# Righ_CH.net
KiCad netlist of a schematic drawn in Altium Designer
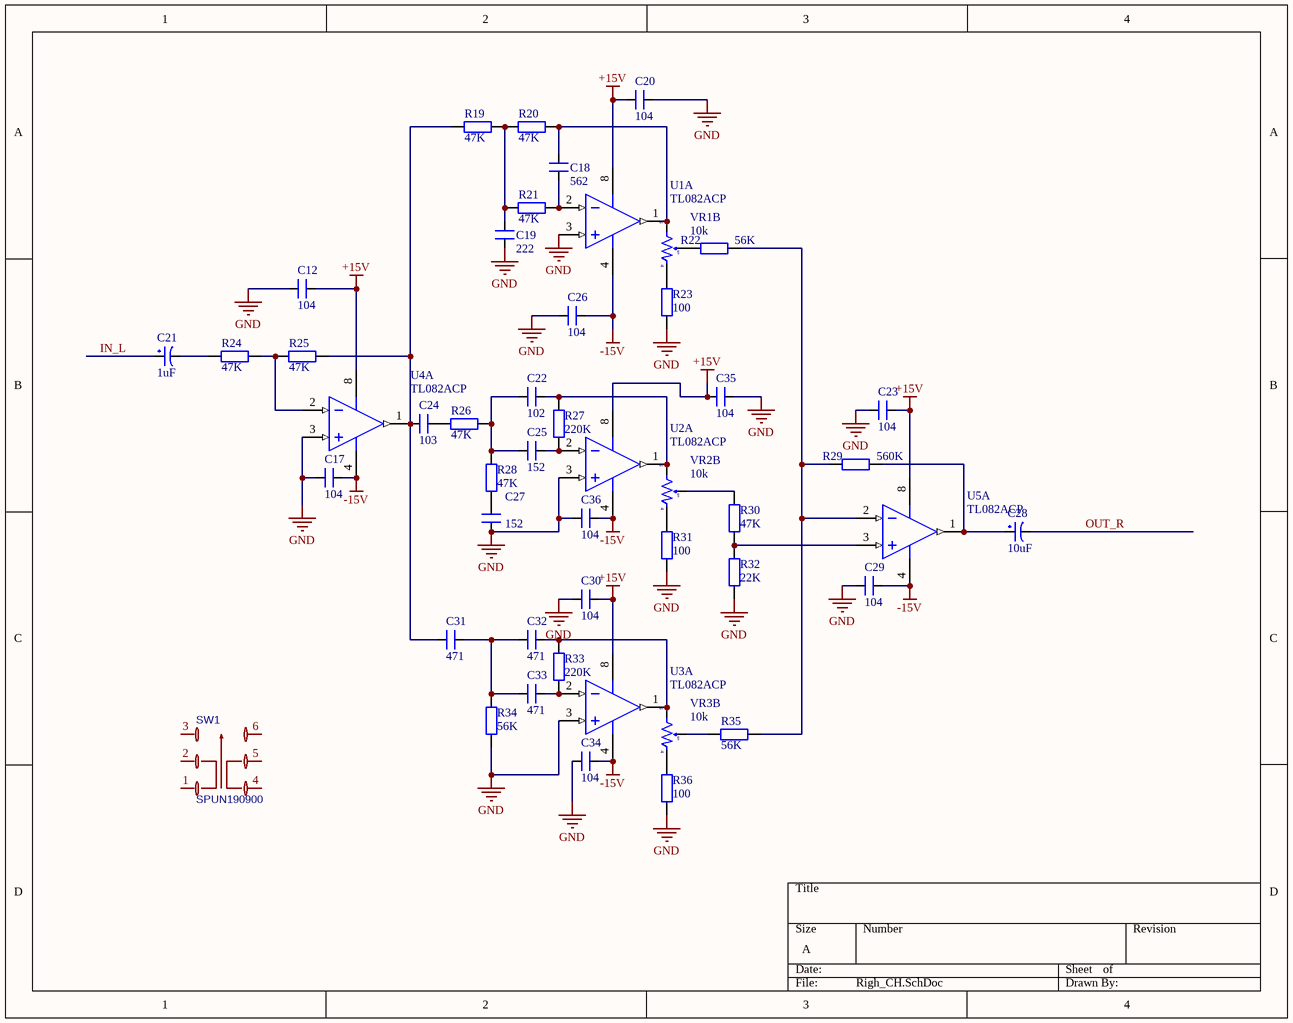
[diagram p0: Righ_CH.SchDoc]

(export (version "E")
  (design (tool "Eeschema 10.0.6"))
  (components
    (comp (ref "C12")
      (value "104")
      (footprint "TU_GOM(104-->105pF)")
      (libsource (lib "MH_DA_THU_VIEN_16122016") (part "TU_MICA_ 104 100V(2A104J)_MH"))
    )
    (comp (ref "C17")
      (value "104")
      (footprint "TU_GOM(104-->105pF)")
      (libsource (lib "MH_DA_THU_VIEN_16122016") (part "TU_MICA_ 104 100V(2A104J)_MH"))
    )
    (comp (ref "C18")
      (value "562")
      (footprint "WIMA-FKP-2-1nF")
      (libsource (lib "MH_DA_THU_VIEN_16122016") (part "TU_MICA_ 104 100V(2A104J)_MH"))
    )
    (comp (ref "C19")
      (value "222")
      (footprint "WIMA-FKP-2-1nF")
      (libsource (lib "MH_DA_THU_VIEN_16122016") (part "TU_MICA_ 104 100V(2A104J)_MH"))
    )
    (comp (ref "C20")
      (value "104")
      (footprint "TU_GOM(104-->105pF)")
      (libsource (lib "MH_DA_THU_VIEN_16122016") (part "TU_MICA_ 104 100V(2A104J)_MH"))
    )
    (comp (ref "C21")
      (value "1uF")
      (footprint "CP1/3.0")
      (description "TU_HOA_4.7uF_100V_MH")
      (libsource (lib "MH_DA_THU_VIEN_16122016") (part "TU_HOA_4.7uF_100V_MH"))
    )
    (comp (ref "C22")
      (value "102")
      (footprint "WIMA-FKP-2-1nF")
      (libsource (lib "MH_DA_THU_VIEN_16122016") (part "TU_MICA_ 104 100V(2A104J)_MH"))
    )
    (comp (ref "C23")
      (value "104")
      (footprint "TU_GOM(104-->105pF)")
      (libsource (lib "MH_DA_THU_VIEN_16122016") (part "TU_MICA_ 104 100V(2A104J)_MH"))
    )
    (comp (ref "C24")
      (value "103")
      (footprint "WIMA-FKP-2-1nF")
      (libsource (lib "MH_DA_THU_VIEN_16122016") (part "TU_MICA_ 104 100V(2A104J)_MH"))
    )
    (comp (ref "C25")
      (value "152")
      (footprint "WIMA-FKP-2-1nF")
      (libsource (lib "MH_DA_THU_VIEN_16122016") (part "TU_MICA_ 104 100V(2A104J)_MH"))
    )
    (comp (ref "C26")
      (value "104")
      (footprint "TU_GOM(104-->105pF)")
      (libsource (lib "MH_DA_THU_VIEN_16122016") (part "TU_MICA_ 104 100V(2A104J)_MH"))
    )
    (comp (ref "C27")
      (value "152")
      (footprint "WIMA-FKP-2-1nF")
      (libsource (lib "MH_DA_THU_VIEN_16122016") (part "TU_MICA_ 104 100V(2A104J)_MH"))
    )
    (comp (ref "C28")
      (value "10uF")
      (footprint "CP1/3.0")
      (description "TU_HOA_4.7uF_100V_MH")
      (libsource (lib "MH_DA_THU_VIEN_16122016") (part "TU_HOA_4.7uF_100V_MH"))
    )
    (comp (ref "C29")
      (value "104")
      (footprint "TU_GOM(104-->105pF)")
      (libsource (lib "MH_DA_THU_VIEN_16122016") (part "TU_MICA_ 104 100V(2A104J)_MH"))
    )
    (comp (ref "C30")
      (value "104")
      (footprint "TU_GOM(104-->105pF)")
      (libsource (lib "MH_DA_THU_VIEN_16122016") (part "TU_MICA_ 104 100V(2A104J)_MH"))
    )
    (comp (ref "C31")
      (value "471")
      (footprint "WIMA-FKP-2-1nF")
      (libsource (lib "MH_DA_THU_VIEN_16122016") (part "TU_MICA_ 104 100V(2A104J)_MH"))
    )
    (comp (ref "C32")
      (value "471")
      (footprint "WIMA-FKP-2-1nF")
      (libsource (lib "MH_DA_THU_VIEN_16122016") (part "TU_MICA_ 104 100V(2A104J)_MH"))
    )
    (comp (ref "C33")
      (value "471")
      (footprint "WIMA-FKP-2-1nF")
      (libsource (lib "MH_DA_THU_VIEN_16122016") (part "TU_MICA_ 104 100V(2A104J)_MH"))
    )
    (comp (ref "C34")
      (value "104")
      (footprint "TU_GOM(104-->105pF)")
      (libsource (lib "MH_DA_THU_VIEN_16122016") (part "TU_MICA_ 104 100V(2A104J)_MH"))
    )
    (comp (ref "C35")
      (value "104")
      (footprint "TU_GOM(104-->105pF)")
      (libsource (lib "MH_DA_THU_VIEN_16122016") (part "TU_MICA_ 104 100V(2A104J)_MH"))
    )
    (comp (ref "C36")
      (value "104")
      (footprint "TU_GOM(104-->105pF)")
      (libsource (lib "MH_DA_THU_VIEN_16122016") (part "TU_MICA_ 104 100V(2A104J)_MH"))
    )
    (comp (ref "R19")
      (value "47K")
      (footprint "TRO_VACH_ 1/4W")
      (description "Resistor")
      (fields (field (name "PUBLISHER") "Altium Limited"))
      (libsource (lib "") (part "TRO_VACH_1/2W_MH_2"))
    )
    (comp (ref "R20")
      (value "47K")
      (footprint "TRO_VACH_ 1/4W")
      (description "Resistor")
      (fields (field (name "PUBLISHER") "Altium Limited"))
      (libsource (lib "") (part "TRO_VACH_1/2W_MH_2"))
    )
    (comp (ref "R21")
      (value "47K")
      (footprint "TRO_VACH_ 1/4W")
      (description "Resistor")
      (fields (field (name "PUBLISHER") "Altium Limited"))
      (libsource (lib "") (part "TRO_VACH_1/2W_MH_2"))
    )
    (comp (ref "R22")
      (value "56K")
      (footprint "TRO_VACH_ 1/4W")
      (description "Resistor")
      (fields (field (name "PUBLISHER") "Altium Limited"))
      (libsource (lib "") (part "TRO_VACH_1/2W_MH_1"))
    )
    (comp (ref "R23")
      (value "100")
      (footprint "TRO_VACH_ 1/4W")
      (description "Resistor")
      (fields (field (name "PUBLISHER") "Altium Limited"))
      (libsource (lib "MH_DA_THU_VIEN_16122016") (part "TRO_VACH_1/2W_MH"))
    )
    (comp (ref "R24")
      (value "47K")
      (footprint "TRO_VACH_ 1/4W")
      (description "Resistor")
      (fields (field (name "PUBLISHER") "Altium Limited"))
      (libsource (lib "") (part "TRO_VACH_1/2W_MH_2"))
    )
    (comp (ref "R25")
      (value "47K")
      (footprint "TRO_VACH_ 1/4W")
      (description "Resistor")
      (fields (field (name "PUBLISHER") "Altium Limited"))
      (libsource (lib "") (part "TRO_VACH_1/2W_MH_2"))
    )
    (comp (ref "R26")
      (value "47K")
      (footprint "TRO_VACH_ 1/4W")
      (description "Resistor")
      (fields (field (name "PUBLISHER") "Altium Limited"))
      (libsource (lib "") (part "TRO_VACH_1/2W_MH_1"))
    )
    (comp (ref "R27")
      (value "220K")
      (footprint "TRO_VACH_ 1/4W")
      (description "Resistor")
      (fields (field (name "PUBLISHER") "Altium Limited"))
      (libsource (lib "MH_DA_THU_VIEN_16122016") (part "TRO_VACH_1/2W_MH"))
    )
    (comp (ref "R28")
      (value "47K")
      (footprint "TRO_VACH_ 1/4W")
      (description "Resistor")
      (fields (field (name "PUBLISHER") "Altium Limited"))
      (libsource (lib "MH_DA_THU_VIEN_16122016") (part "TRO_VACH_1/2W_MH"))
    )
    (comp (ref "R29")
      (value "560K")
      (footprint "TRO_VACH_ 1/4W")
      (description "Resistor")
      (fields (field (name "PUBLISHER") "Altium Limited"))
      (libsource (lib "") (part "TRO_VACH_1/2W_MH_1"))
    )
    (comp (ref "R30")
      (value "47K")
      (footprint "TRO_VACH_ 1/4W")
      (description "Resistor")
      (fields (field (name "PUBLISHER") "Altium Limited"))
      (libsource (lib "MH_DA_THU_VIEN_16122016") (part "TRO_VACH_1/2W_MH"))
    )
    (comp (ref "R31")
      (value "100")
      (footprint "TRO_VACH_ 1/4W")
      (description "Resistor")
      (fields (field (name "PUBLISHER") "Altium Limited"))
      (libsource (lib "MH_DA_THU_VIEN_16122016") (part "TRO_VACH_1/2W_MH"))
    )
    (comp (ref "R32")
      (value "22K")
      (footprint "TRO_VACH_ 1/4W")
      (description "Resistor")
      (fields (field (name "PUBLISHER") "Altium Limited"))
      (libsource (lib "MH_DA_THU_VIEN_16122016") (part "TRO_VACH_1/2W_MH"))
    )
    (comp (ref "R33")
      (value "220K")
      (footprint "TRO_VACH_ 1/4W")
      (description "Resistor")
      (fields (field (name "PUBLISHER") "Altium Limited"))
      (libsource (lib "MH_DA_THU_VIEN_16122016") (part "TRO_VACH_1/2W_MH"))
    )
    (comp (ref "R34")
      (value "56K")
      (footprint "TRO_VACH_ 1/4W")
      (description "Resistor")
      (fields (field (name "PUBLISHER") "Altium Limited"))
      (libsource (lib "MH_DA_THU_VIEN_16122016") (part "TRO_VACH_1/2W_MH"))
    )
    (comp (ref "R35")
      (value "56K")
      (footprint "TRO_VACH_ 1/4W")
      (description "Resistor")
      (fields (field (name "PUBLISHER") "Altium Limited"))
      (libsource (lib "") (part "TRO_VACH_1/2W_MH_1"))
    )
    (comp (ref "R36")
      (value "100")
      (footprint "TRO_VACH_ 1/4W")
      (description "Resistor")
      (fields (field (name "PUBLISHER") "Altium Limited"))
      (libsource (lib "MH_DA_THU_VIEN_16122016") (part "TRO_VACH_1/2W_MH"))
    )
    (comp (ref "SW1")
      (value "SPUN190900")
      (footprint "SW-DIP-P42X10")
      (fields (field (name "BOM_SUPPLIER PART") "C278339") (field (name "CONTRIBUTOR") "LCSC"))
      (libsource (lib "Schlib1") (part "SPUN190900"))
    )
    (comp (ref "U1")
      (value "TL082ACP")
      (footprint "DIP8")
      (description "JFET-Input Operational Amplifier")
      (fields (field (name "PUBLISHER") "Altium Limited"))
      (libsource (lib "Schlib1") (part "TL082ACP"))
    )
    (comp (ref "U2")
      (value "TL082ACP")
      (footprint "DIP8")
      (description "JFET-Input Operational Amplifier")
      (fields (field (name "PUBLISHER") "Altium Limited"))
      (libsource (lib "Schlib1") (part "TL082ACP"))
    )
    (comp (ref "U3")
      (value "TL082ACP")
      (footprint "DIP8")
      (description "JFET-Input Operational Amplifier")
      (fields (field (name "PUBLISHER") "Altium Limited"))
      (libsource (lib "Schlib1") (part "TL082ACP"))
    )
    (comp (ref "U4")
      (value "TL082ACP")
      (footprint "DIP8")
      (description "JFET-Input Operational Amplifier")
      (fields (field (name "PUBLISHER") "Altium Limited"))
      (libsource (lib "Schlib1") (part "TL082ACP"))
    )
    (comp (ref "U5")
      (value "TL082ACP")
      (footprint "DIP8")
      (description "JFET-Input Operational Amplifier")
      (fields (field (name "PUBLISHER") "Altium Limited"))
      (libsource (lib "Schlib1") (part "TL082ACP"))
    )
    (comp (ref "VR1")
      (value "10k")
      (footprint "9011")
      (description "Triet Ap Doi 10k")
      (libsource (lib "Schlib1") (part "Triet Ap Doi 10k_MH"))
    )
    (comp (ref "VR2")
      (value "10k")
      (footprint "9011")
      (description "Triet Ap Doi 10k")
      (libsource (lib "Schlib1") (part "Triet Ap Doi 10k_MH"))
    )
    (comp (ref "VR3")
      (value "10k")
      (footprint "9011")
      (description "Triet Ap Doi 10k")
      (libsource (lib "Schlib1") (part "Triet Ap Doi 10k_MH"))
    )
  )
  (nets
    (net (code "1") (name "+15V") (class "Default")
      (node (ref "C12") (pin "2") (pinfunction "2_2") (pintype "passive"))
      (node (ref "C20") (pin "1") (pinfunction "1_1") (pintype "passive"))
      (node (ref "C23") (pin "2") (pinfunction "2_2") (pintype "passive"))
      (node (ref "C30") (pin "2") (pinfunction "2_2") (pintype "passive"))
      (node (ref "C35") (pin "2") (pinfunction "2_2") (pintype "passive"))
      (node (ref "U1") (pin "8") (pinfunction "V+_8") (pintype "power_in"))
      (node (ref "U2") (pin "8") (pinfunction "V+_8") (pintype "power_in"))
      (node (ref "U3") (pin "8") (pinfunction "V+_8") (pintype "power_in"))
      (node (ref "U4") (pin "8") (pinfunction "V+_8") (pintype "power_in"))
      (node (ref "U5") (pin "8") (pinfunction "V+_8") (pintype "power_in"))
    )
    (net (code "2") (name "-15V") (class "Default")
      (node (ref "C17") (pin "2") (pinfunction "2_2") (pintype "passive"))
      (node (ref "C26") (pin "2") (pinfunction "2_2") (pintype "passive"))
      (node (ref "C29") (pin "2") (pinfunction "2_2") (pintype "passive"))
      (node (ref "C34") (pin "2") (pinfunction "2_2") (pintype "passive"))
      (node (ref "C36") (pin "1") (pinfunction "1_1") (pintype "passive"))
      (node (ref "U1") (pin "4") (pinfunction "V-_4") (pintype "power_in"))
      (node (ref "U2") (pin "4") (pinfunction "V-_4") (pintype "power_in"))
      (node (ref "U3") (pin "4") (pinfunction "V-_4") (pintype "power_in"))
      (node (ref "U4") (pin "4") (pinfunction "V-_4") (pintype "power_in"))
      (node (ref "U5") (pin "4") (pinfunction "V-_4") (pintype "power_in"))
    )
    (net (code "3") (name "/IN_L") (class "Default")
      (node (ref "C21") (pin "1") (pinfunction "1_1") (pintype "passive"))
    )
    (net (code "4") (name "/OUT_R") (class "Default")
      (node (ref "C28") (pin "2") (pinfunction "2_2") (pintype "passive"))
    )
    (net (code "5") (name "GND") (class "Default")
      (node (ref "C12") (pin "1") (pinfunction "1_1") (pintype "passive"))
      (node (ref "C17") (pin "1") (pinfunction "1_1") (pintype "passive"))
      (node (ref "C19") (pin "1") (pinfunction "1_1") (pintype "passive"))
      (node (ref "C20") (pin "2") (pinfunction "2_2") (pintype "passive"))
      (node (ref "C23") (pin "1") (pinfunction "1_1") (pintype "passive"))
      (node (ref "C26") (pin "1") (pinfunction "1_1") (pintype "passive"))
      (node (ref "C27") (pin "2") (pinfunction "2_2") (pintype "passive"))
      (node (ref "C29") (pin "1") (pinfunction "1_1") (pintype "passive"))
      (node (ref "C30") (pin "1") (pinfunction "1_1") (pintype "passive"))
      (node (ref "C34") (pin "1") (pinfunction "1_1") (pintype "passive"))
      (node (ref "C35") (pin "1") (pinfunction "1_1") (pintype "passive"))
      (node (ref "C36") (pin "2") (pinfunction "2_2") (pintype "passive"))
      (node (ref "R23") (pin "1") (pinfunction "1_1") (pintype "passive"))
      (node (ref "R31") (pin "1") (pinfunction "1_1") (pintype "passive"))
      (node (ref "R32") (pin "1") (pinfunction "1_1") (pintype "passive"))
      (node (ref "R34") (pin "1") (pinfunction "1_1") (pintype "passive"))
      (node (ref "R36") (pin "1") (pinfunction "1_1") (pintype "passive"))
      (node (ref "U1") (pin "3") (pinfunction "IN+_3") (pintype "input"))
      (node (ref "U2") (pin "3") (pinfunction "IN+_3") (pintype "input"))
      (node (ref "U3") (pin "3") (pinfunction "IN+_3") (pintype "input"))
      (node (ref "U4") (pin "3") (pinfunction "IN+_3") (pintype "input"))
    )
    (net (code "6") (name "Net-(C19-Pad2)") (class "Default")
      (node (ref "C19") (pin "2") (pinfunction "2_2") (pintype "passive"))
      (node (ref "R19") (pin "2") (pinfunction "2_2") (pintype "passive"))
      (node (ref "R20") (pin "1") (pinfunction "1_1") (pintype "passive"))
      (node (ref "R21") (pin "1") (pinfunction "1_1") (pintype "passive"))
    )
    (net (code "7") (name "Net-(C21-Pad2)") (class "Default")
      (node (ref "C21") (pin "2") (pinfunction "2_2") (pintype "passive"))
      (node (ref "R24") (pin "1") (pinfunction "1_1") (pintype "passive"))
    )
    (net (code "8") (name "Net-(C22-Pad2)") (class "Default")
      (node (ref "C22") (pin "2") (pinfunction "2_2") (pintype "passive"))
      (node (ref "C25") (pin "2") (pinfunction "2_2") (pintype "passive"))
      (node (ref "R26") (pin "1") (pinfunction "1_1") (pintype "passive"))
      (node (ref "R28") (pin "2") (pinfunction "2_2") (pintype "passive"))
    )
    (net (code "9") (name "Net-(C24-Pad2)") (class "Default")
      (node (ref "C24") (pin "2") (pinfunction "2_2") (pintype "passive"))
      (node (ref "R26") (pin "2") (pinfunction "2_2") (pintype "passive"))
    )
    (net (code "10") (name "Net-(C27-Pad1)") (class "Default")
      (node (ref "C27") (pin "1") (pinfunction "1_1") (pintype "passive"))
      (node (ref "R28") (pin "1") (pinfunction "1_1") (pintype "passive"))
    )
    (net (code "11") (name "Net-(C31-Pad1)") (class "Default")
      (node (ref "C31") (pin "1") (pinfunction "1_1") (pintype "passive"))
      (node (ref "C32") (pin "2") (pinfunction "2_2") (pintype "passive"))
      (node (ref "C33") (pin "2") (pinfunction "2_2") (pintype "passive"))
      (node (ref "R34") (pin "2") (pinfunction "2_2") (pintype "passive"))
    )
    (net (code "12") (name "Net-(R22-Pad2)") (class "Default")
      (node (ref "R22") (pin "2") (pinfunction "2_2") (pintype "passive"))
      (node (ref "VR1") (pin "5") (pinfunction "5_5") (pintype "passive"))
    )
    (net (code "13") (name "Net-(R23-Pad2)") (class "Default")
      (node (ref "R23") (pin "2") (pinfunction "2_2") (pintype "passive"))
      (node (ref "VR1") (pin "4") (pinfunction "4_4") (pintype "passive"))
    )
    (net (code "14") (name "Net-(R30-Pad2)") (class "Default")
      (node (ref "R30") (pin "2") (pinfunction "2_2") (pintype "passive"))
      (node (ref "VR2") (pin "5") (pinfunction "5_5") (pintype "passive"))
    )
    (net (code "15") (name "Net-(R31-Pad2)") (class "Default")
      (node (ref "R31") (pin "2") (pinfunction "2_2") (pintype "passive"))
      (node (ref "VR2") (pin "4") (pinfunction "4_4") (pintype "passive"))
    )
    (net (code "16") (name "Net-(R35-Pad2)") (class "Default")
      (node (ref "R35") (pin "2") (pinfunction "2_2") (pintype "passive"))
      (node (ref "VR3") (pin "5") (pinfunction "5_5") (pintype "passive"))
    )
    (net (code "17") (name "Net-(R36-Pad2)") (class "Default")
      (node (ref "R36") (pin "2") (pinfunction "2_2") (pintype "passive"))
      (node (ref "VR3") (pin "4") (pinfunction "4_4") (pintype "passive"))
    )
    (net (code "18") (name "Net-(U1A-IN-)") (class "Default")
      (node (ref "C18") (pin "1") (pinfunction "1_1") (pintype "passive"))
      (node (ref "R21") (pin "2") (pinfunction "2_2") (pintype "passive"))
      (node (ref "U1") (pin "2") (pinfunction "IN-_2") (pintype "input"))
    )
    (net (code "19") (name "Net-(U1A-OUT)") (class "Default")
      (node (ref "C18") (pin "2") (pinfunction "2_2") (pintype "passive"))
      (node (ref "R20") (pin "2") (pinfunction "2_2") (pintype "passive"))
      (node (ref "U1") (pin "1") (pinfunction "OUT_1") (pintype "output"))
      (node (ref "VR1") (pin "6") (pinfunction "6_6") (pintype "passive"))
    )
    (net (code "20") (name "Net-(U2A-IN-)") (class "Default")
      (node (ref "C25") (pin "1") (pinfunction "1_1") (pintype "passive"))
      (node (ref "R27") (pin "1") (pinfunction "1_1") (pintype "passive"))
      (node (ref "U2") (pin "2") (pinfunction "IN-_2") (pintype "input"))
    )
    (net (code "21") (name "Net-(U2A-OUT)") (class "Default")
      (node (ref "C22") (pin "1") (pinfunction "1_1") (pintype "passive"))
      (node (ref "R27") (pin "2") (pinfunction "2_2") (pintype "passive"))
      (node (ref "U2") (pin "1") (pinfunction "OUT_1") (pintype "output"))
      (node (ref "VR2") (pin "6") (pinfunction "6_6") (pintype "passive"))
    )
    (net (code "22") (name "Net-(U3A-IN-)") (class "Default")
      (node (ref "C33") (pin "1") (pinfunction "1_1") (pintype "passive"))
      (node (ref "R33") (pin "1") (pinfunction "1_1") (pintype "passive"))
      (node (ref "U3") (pin "2") (pinfunction "IN-_2") (pintype "input"))
    )
    (net (code "23") (name "Net-(U3A-OUT)") (class "Default")
      (node (ref "C32") (pin "1") (pinfunction "1_1") (pintype "passive"))
      (node (ref "R33") (pin "2") (pinfunction "2_2") (pintype "passive"))
      (node (ref "U3") (pin "1") (pinfunction "OUT_1") (pintype "output"))
      (node (ref "VR3") (pin "6") (pinfunction "6_6") (pintype "passive"))
    )
    (net (code "24") (name "Net-(U4A-IN-)") (class "Default")
      (node (ref "R24") (pin "2") (pinfunction "2_2") (pintype "passive"))
      (node (ref "R25") (pin "1") (pinfunction "1_1") (pintype "passive"))
      (node (ref "U4") (pin "2") (pinfunction "IN-_2") (pintype "input"))
    )
    (net (code "25") (name "Net-(U4A-OUT)") (class "Default")
      (node (ref "C24") (pin "1") (pinfunction "1_1") (pintype "passive"))
      (node (ref "C31") (pin "2") (pinfunction "2_2") (pintype "passive"))
      (node (ref "R19") (pin "1") (pinfunction "1_1") (pintype "passive"))
      (node (ref "R25") (pin "2") (pinfunction "2_2") (pintype "passive"))
      (node (ref "U4") (pin "1") (pinfunction "OUT_1") (pintype "output"))
    )
    (net (code "26") (name "Net-(U5A-IN+)") (class "Default")
      (node (ref "R30") (pin "1") (pinfunction "1_1") (pintype "passive"))
      (node (ref "R32") (pin "2") (pinfunction "2_2") (pintype "passive"))
      (node (ref "U5") (pin "3") (pinfunction "IN+_3") (pintype "input"))
    )
    (net (code "27") (name "Net-(U5A-IN-)") (class "Default")
      (node (ref "R22") (pin "1") (pinfunction "1_1") (pintype "passive"))
      (node (ref "R29") (pin "2") (pinfunction "2_2") (pintype "passive"))
      (node (ref "R35") (pin "1") (pinfunction "1_1") (pintype "passive"))
      (node (ref "U5") (pin "2") (pinfunction "IN-_2") (pintype "input"))
    )
    (net (code "28") (name "Net-(U5A-OUT)") (class "Default")
      (node (ref "C28") (pin "1") (pinfunction "1_1") (pintype "passive"))
      (node (ref "R29") (pin "1") (pinfunction "1_1") (pintype "passive"))
      (node (ref "U5") (pin "1") (pinfunction "OUT_1") (pintype "output"))
    )
    (net (code "29") (name "unconnected-(SW1-Pad1)") (class "Default")
      (node (ref "SW1") (pin "1") (pinfunction "1_1") (pintype "passive"))
    )
    (net (code "30") (name "unconnected-(SW1-Pad2)") (class "Default")
      (node (ref "SW1") (pin "2") (pinfunction "2_2") (pintype "passive"))
    )
    (net (code "31") (name "unconnected-(SW1-Pad3)") (class "Default")
      (node (ref "SW1") (pin "3") (pinfunction "3_3") (pintype "passive"))
    )
    (net (code "32") (name "unconnected-(SW1-Pad4)") (class "Default")
      (node (ref "SW1") (pin "4") (pinfunction "4_4") (pintype "passive"))
    )
    (net (code "33") (name "unconnected-(SW1-Pad5)") (class "Default")
      (node (ref "SW1") (pin "5") (pinfunction "5_5") (pintype "passive"))
    )
    (net (code "34") (name "unconnected-(SW1-Pad6)") (class "Default")
      (node (ref "SW1") (pin "6") (pinfunction "6_6") (pintype "passive"))
    )
  )
)
